# Mcu.net
KiCad netlist of a schematic drawn in Altium Designer
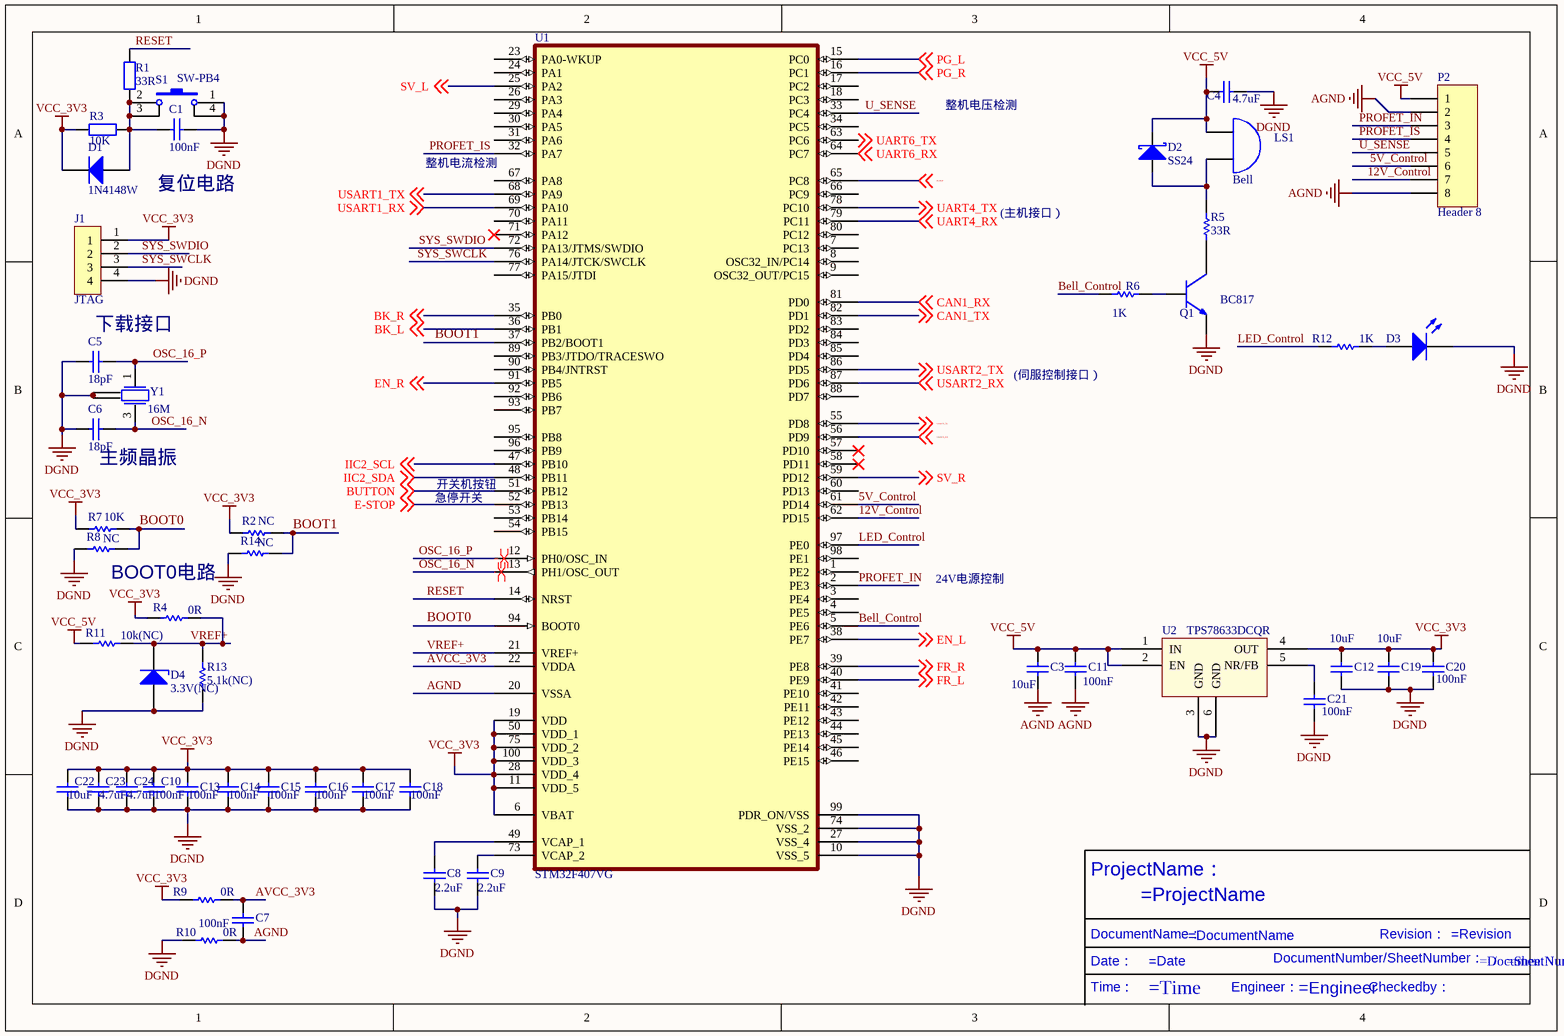
[diagram p0: Mcu.SchDoc]

(export (version "E")
  (design (tool "Eeschema 10.0.6"))
  (components
    (comp (ref "C1")
      (value "100nF")
      (footprint "C-RAD-0805")
      (description "无极性电容")
      (fields (field (name "Comment") "100nF/±10%/50Vdc") (field (name "PUBLISHER") "Altium Limited"))
      (libsource (lib "Compiled_Libraries") (part "Cap"))
    )
    (comp (ref "C3")
      (value "10uF")
      (footprint "C-RAD-0805")
      (description "Capacitor")
      (fields (field (name "Comment") "10uF/±10%/50Vdc") (field (name "PUBLISHER") "Altium Limited"))
      (libsource (lib "STS-TDOA") (part "Cap"))
    )
    (comp (ref "C4")
      (value "4.7uF")
      (footprint "C-RAD-0805")
      (description "Capacitor")
      (fields (field (name "Comment") "4.7uF/±10%/50Vdc") (field (name "PUBLISHER") "Altium Limited"))
      (libsource (lib "boocax_schlib") (part "Cap"))
    )
    (comp (ref "C5")
      (value "18pF")
      (footprint "C-RAD-0805")
      (description "无极性电容")
      (fields (field (name "Comment") "18pF/±10%/25Vdc") (field (name "PUBLISHER") "Altium Limited"))
      (libsource (lib "Compiled_Libraries") (part "Cap"))
    )
    (comp (ref "C6")
      (value "18pF")
      (footprint "C-RAD-0805")
      (description "无极性电容")
      (fields (field (name "Comment") "18pF/±10%/25Vdc") (field (name "PUBLISHER") "Altium Limited"))
      (libsource (lib "Compiled_Libraries") (part "Cap"))
    )
    (comp (ref "C7")
      (value "100nF")
      (footprint "C-RAD-0805")
      (description "Capacitor")
      (fields (field (name "Comment") "100nF/±10%/50Vdc") (field (name "PUBLISHER") "Altium Limited"))
      (libsource (lib "boocax_schlib") (part "Cap"))
    )
    (comp (ref "C8")
      (value "2.2uF")
      (footprint "C-RAD-0805")
      (description "Capacitor")
      (fields (field (name "Comment") "2.2uF/±10%/50Vdc") (field (name "PUBLISHER") "Altium Limited"))
      (libsource (lib "boocax_schlib") (part "Cap"))
    )
    (comp (ref "C9")
      (value "2.2uF")
      (footprint "C-RAD-0805")
      (description "Capacitor")
      (fields (field (name "Comment") "2.2uF/±10%/50Vdc") (field (name "PUBLISHER") "Altium Limited"))
      (libsource (lib "boocax_schlib") (part "Cap"))
    )
    (comp (ref "C10")
      (value "100nF")
      (footprint "C-RAD-0805")
      (description "Capacitor")
      (fields (field (name "Comment") "100nF/±10%/50Vdc") (field (name "PUBLISHER") "Altium Limited"))
      (libsource (lib "boocax_schlib") (part "Cap"))
    )
    (comp (ref "C11")
      (value "100nF")
      (footprint "C-RAD-0805")
      (description "Capacitor")
      (fields (field (name "Comment") "100nF/±10%/50Vdc") (field (name "PUBLISHER") "Altium Limited"))
      (libsource (lib "STS-TDOA") (part "Cap"))
    )
    (comp (ref "C12")
      (value "10uF")
      (footprint "C-RAD-0805")
      (description "Capacitor,33uF / ESR 1.69m /10Vdc,C2012X5R1A336M125AC")
      (fields (field (name "Comment") "10uF/±10%/50Vdc") (field (name "PUBLISHER") "Altium Limited"))
      (libsource (lib "STS-TDOA") (part "Cap"))
    )
    (comp (ref "C13")
      (value "100nF")
      (footprint "C-RAD-0805")
      (description "Capacitor")
      (fields (field (name "Comment") "100nF/±10%/50Vdc") (field (name "PUBLISHER") "Altium Limited"))
      (libsource (lib "boocax_schlib") (part "Cap"))
    )
    (comp (ref "C14")
      (value "100nF")
      (footprint "C-RAD-0805")
      (description "Capacitor")
      (fields (field (name "Comment") "100nF/±10%/50Vdc") (field (name "PUBLISHER") "Altium Limited"))
      (libsource (lib "boocax_schlib") (part "Cap"))
    )
    (comp (ref "C15")
      (value "100nF")
      (footprint "C-RAD-0805")
      (description "Capacitor")
      (fields (field (name "Comment") "100nF/±10%/50Vdc") (field (name "PUBLISHER") "Altium Limited"))
      (libsource (lib "boocax_schlib") (part "Cap"))
    )
    (comp (ref "C16")
      (value "100nF")
      (footprint "C-RAD-0805")
      (description "Capacitor")
      (fields (field (name "Comment") "100nF/±10%/50Vdc") (field (name "PUBLISHER") "Altium Limited"))
      (libsource (lib "boocax_schlib") (part "Cap"))
    )
    (comp (ref "C17")
      (value "100nF")
      (footprint "C-RAD-0805")
      (description "Capacitor")
      (fields (field (name "Comment") "100nF/±10%/50Vdc") (field (name "PUBLISHER") "Altium Limited"))
      (libsource (lib "boocax_schlib") (part "Cap"))
    )
    (comp (ref "C18")
      (value "100nF")
      (footprint "C-RAD-0805")
      (description "Capacitor")
      (fields (field (name "Comment") "100nF/±10%/50Vdc") (field (name "PUBLISHER") "Altium Limited"))
      (libsource (lib "boocax_schlib") (part "Cap"))
    )
    (comp (ref "C19")
      (value "10uF")
      (footprint "C-RAD-0805")
      (description "Capacitor,33uF / ESR 1.69m /10Vdc,C2012X5R1A336M125AC")
      (fields (field (name "Comment") "10uF/±10%/50Vdc") (field (name "PUBLISHER") "Altium Limited"))
      (libsource (lib "STS-TDOA") (part "Cap"))
    )
    (comp (ref "C20")
      (value "100nF")
      (footprint "C-RAD-0805")
      (description "Capacitor")
      (fields (field (name "Comment") "100nF/±10%/50Vdc") (field (name "PUBLISHER") "Altium Limited"))
      (libsource (lib "STS-TDOA") (part "Cap"))
    )
    (comp (ref "C21")
      (value "100nF")
      (footprint "C-RAD-0805")
      (description "Capacitor")
      (fields (field (name "Comment") "100nF/±10%/50Vdc") (field (name "PUBLISHER") "Altium Limited"))
      (libsource (lib "STS-TDOA") (part "Cap"))
    )
    (comp (ref "C22")
      (value "10uF")
      (footprint "C-RAD-0805")
      (description "Capacitor")
      (fields (field (name "Comment") "10uF/±10%/50Vdc") (field (name "PUBLISHER") "Altium Limited"))
      (libsource (lib "boocax_schlib") (part "Cap"))
    )
    (comp (ref "C23")
      (value "4.7uF")
      (footprint "C-RAD-0805")
      (description "Capacitor")
      (fields (field (name "Comment") "4.7uF/±10%/50Vdc") (field (name "PUBLISHER") "Altium Limited"))
      (libsource (lib "boocax_schlib") (part "Cap"))
    )
    (comp (ref "C24")
      (value "4.7uF")
      (footprint "C-RAD-0805")
      (description "Capacitor")
      (fields (field (name "Comment") "4.7uF/±10%/50Vdc") (field (name "PUBLISHER") "Altium Limited"))
      (libsource (lib "boocax_schlib") (part "Cap"))
    )
    (comp (ref "D1")
      (value "1N4148W")
      (footprint "DIODE-1206")
      (description "二极管")
      (fields (field (name "PUBLISHER") "Altium Limited"))
      (libsource (lib "founder") (part "Diode"))
    )
    (comp (ref "D2")
      (value "SS24")
      (footprint "DIODE-SMA")
      (description "肖特基二极管")
      (fields (field (name "Comment") "Diode-Schottky") (field (name "PUBLISHER") "Altium Limited"))
      (libsource (lib "boocax_schlib-20171017-1-dkw") (part "Diode-Schottky"))
    )
    (comp (ref "D3")
      (value "LED0")
      (footprint "LED_0805")
      (description "发光二极管")
      (fields (field (name "PUBLISHER") "Altium Limited"))
      (libsource (lib "founder") (part "LED0"))
    )
    (comp (ref "D4")
      (value "3.3V(NC)")
      (footprint "DIODE-1206")
      (description "稳压二极管")
      (fields (field (name "Comment") "Diode-Z") (field (name "PUBLISHER") "Altium Limited"))
      (libsource (lib "Fszhang") (part "Diode-Z"))
    )
    (comp (ref "J1")
      (value "JTAG")
      (footprint "PORT-SIP4-2.54")
      (libsource (lib "boocax_schlib") (part "Conn_1*4_1"))
    )
    (comp (ref "LS1")
      (value "Bell")
      (footprint "PIN2")
      (description "Electrical Bell")
      (fields (field (name "PUBLISHER") "Altium Limited"))
      (libsource (lib "Miscellaneous Devices") (part "Bell"))
    )
    (comp (ref "P2")
      (value "Header 8")
      (footprint "SM08B-PBV")
      (description "Header, 8-Pin")
      (fields (field (name "PUBLISHER") "Altium Limited"))
      (libsource (lib "fszhang") (part "Header 8"))
    )
    (comp (ref "Q1")
      (value "BC817")
      (footprint "SOT-23_N")
      (description "NPN 45V 功耗 310mW")
      (libsource (lib "Schlib1") (part "mNPN"))
    )
    (comp (ref "R1")
      (value "33R")
      (footprint "0805-1")
      (description "贴片电阻")
      (fields (field (name "Comment") "33R 5% 1/16W 0805") (field (name "PUBLISHER") "Altium Limited"))
      (libsource (lib "Compiled_Libraries") (part "Res1"))
    )
    (comp (ref "R2")
      (value "NC")
      (footprint "0805-1")
      (description "Resistor")
      (fields (field (name "Comment") "10K 5% 1/16W 0805(NC)") (field (name "PUBLISHER") "Altium Limited"))
      (libsource (lib "boocax_schlib") (part "Res1"))
    )
    (comp (ref "R3")
      (value "10K")
      (footprint "0805-1")
      (description "贴片电阻")
      (fields (field (name "Comment") "10K 5% 1/16W 0805") (field (name "PUBLISHER") "Altium Limited"))
      (libsource (lib "") (part "Res1_1"))
    )
    (comp (ref "R4")
      (value "0R")
      (footprint "0805-1")
      (description "Resistor")
      (fields (field (name "Comment") "0R 5% 1/16W 0805(NC)") (field (name "PUBLISHER") "Altium Limited"))
      (libsource (lib "boocax_schlib") (part "Res1"))
    )
    (comp (ref "R5")
      (value "33R")
      (footprint "0805-1")
      (description "Resistor")
      (fields (field (name "Comment") "33R 5% 1/16W 0805") (field (name "PUBLISHER") "Altium Limited"))
      (libsource (lib "boocax_schlib") (part "Res1"))
    )
    (comp (ref "R6")
      (value "1K")
      (footprint "0805-1")
      (description "Resistor")
      (fields (field (name "Comment") "1K 5% 1/16W 0805") (field (name "PUBLISHER") "Altium Limited"))
      (libsource (lib "boocax_schlib") (part "Res1"))
    )
    (comp (ref "R7")
      (value "10K")
      (footprint "0805-1")
      (description "Resistor")
      (fields (field (name "Comment") "10K 5% 1/16W 0805") (field (name "PUBLISHER") "Altium Limited"))
      (libsource (lib "boocax_schlib") (part "Res1"))
    )
    (comp (ref "R8")
      (value "NC")
      (footprint "0805-1")
      (description "Resistor")
      (fields (field (name "Comment") "10K 5% 1/16W 0805(NC)") (field (name "PUBLISHER") "Altium Limited"))
      (libsource (lib "boocax_schlib") (part "Res1"))
    )
    (comp (ref "R9")
      (value "0R")
      (footprint "0805-1")
      (description "Resistor")
      (fields (field (name "Comment") "0R 5% 1/16W 0805") (field (name "PUBLISHER") "Altium Limited"))
      (libsource (lib "boocax_schlib") (part "Res1"))
    )
    (comp (ref "R10")
      (value "0R")
      (footprint "0805-1")
      (description "Resistor")
      (fields (field (name "Comment") "0R 5% 1/16W 0805") (field (name "PUBLISHER") "Altium Limited"))
      (libsource (lib "boocax_schlib") (part "Res1"))
    )
    (comp (ref "R11")
      (value "10k(NC)")
      (footprint "0805-1")
      (description "Resistor")
      (fields (field (name "Comment") "10K 5% 1/16W 0805(NC)") (field (name "PUBLISHER") "Altium Limited"))
      (libsource (lib "boocax_schlib") (part "Res1"))
    )
    (comp (ref "R12")
      (value "1K")
      (footprint "0805-1")
      (description "Resistor")
      (fields (field (name "Comment") "1K 5% 1/16W 0805") (field (name "PUBLISHER") "Altium Limited"))
      (libsource (lib "boocax_schlib") (part "Res1"))
    )
    (comp (ref "R13")
      (value "5.1k(NC)")
      (footprint "0805-1")
      (description "Resistor")
      (fields (field (name "Comment") "5.1K 5% 1/16W 0805(NC)") (field (name "PUBLISHER") "Altium Limited"))
      (libsource (lib "boocax_schlib") (part "Res1"))
    )
    (comp (ref "R14")
      (value "NC")
      (footprint "0805-1")
      (description "Resistor")
      (fields (field (name "Comment") "10K 5% 1/16W 0805(NC)") (field (name "PUBLISHER") "Altium Limited"))
      (libsource (lib "boocax_schlib") (part "Res1"))
    )
    (comp (ref "S1")
      (value "SW-PB4")
      (footprint "RESET-SMD-1O4")
      (description "微动开关")
      (fields (field (name "PUBLISHER") "Altium Limited"))
      (libsource (lib "boocax_schlib") (part "SW-PB4"))
    )
    (comp (ref "U1")
      (value "STM32F407VG")
      (footprint "100T1_N")
      (description "主控MCU")
      (libsource (lib "boocax_schlib") (part "STM32F407VG"))
    )
    (comp (ref "U2")
      (value "TPS78633DCQR")
      (footprint "SOT-223-G6")
      (description "3.3V稳压芯片 1.5A输出")
      (fields (field (name "PUBLISHER") "*"))
      (libsource (lib "Compiled_Libraries") (part "TPS78633DCQR"))
    )
    (comp (ref "Y1")
      (value "16M")
      (footprint "EPSON-16M")
      (description "晶振")
      (fields (field (name "Comment") "XTAL-16M"))
      (libsource (lib "fszhang") (part "XTAL-4PIN"))
    )
  )
  (nets
    (net (code "1") (name "/5V_Control") (class "Default")
      (node (ref "P2") (pin "6") (pinfunction "6_6") (pintype "passive"))
      (node (ref "U1") (pin "61") (pinfunction "PD14_61") (pintype "bidirectional"))
    )
    (net (code "2") (name "/12V_Control") (class "Default")
      (node (ref "P2") (pin "7") (pinfunction "7_7") (pintype "passive"))
      (node (ref "U1") (pin "62") (pinfunction "PD15_62") (pintype "bidirectional"))
    )
    (net (code "11") (name "/AVCC_3V3") (class "Default")
      (node (ref "C7") (pin "2") (pinfunction "2_2") (pintype "passive"))
      (node (ref "R9") (pin "1") (pinfunction "1_1") (pintype "passive"))
      (node (ref "U1") (pin "22") (pinfunction "VDDA_22") (pintype "power_in"))
    )
    (net (code "12") (name "/BOOT0") (class "Default")
      (node (ref "R7") (pin "2") (pinfunction "2_2") (pintype "passive"))
      (node (ref "R8") (pin "1") (pinfunction "1_1") (pintype "passive"))
      (node (ref "U1") (pin "94") (pinfunction "BOOT0_94") (pintype "input"))
    )
    (net (code "13") (name "/BOOT1") (class "Default")
      (node (ref "R14") (pin "1") (pinfunction "1_1") (pintype "passive"))
      (node (ref "R2") (pin "2") (pinfunction "2_2") (pintype "passive"))
      (node (ref "U1") (pin "37") (pinfunction "PB2/BOOT1_37") (pintype "bidirectional"))
    )
    (net (code "14") (name "/Bell_Control") (class "Default")
      (node (ref "R6") (pin "2") (pinfunction "2_2") (pintype "passive"))
      (node (ref "U1") (pin "5") (pinfunction "PE6_5") (pintype "bidirectional"))
    )
    (net (code "20") (name "/LED_Control") (class "Default")
      (node (ref "R12") (pin "2") (pinfunction "2_2") (pintype "passive"))
      (node (ref "U1") (pin "97") (pinfunction "PE0_97") (pintype "bidirectional"))
    )
    (net (code "21") (name "/OSC_16_N") (class "Default")
      (node (ref "C6") (pin "1") (pinfunction "1_1") (pintype "passive"))
      (node (ref "U1") (pin "13") (pinfunction "PH1/OSC_OUT_13") (pintype "output"))
      (node (ref "Y1") (pin "3") (pinfunction "3_3") (pintype "passive"))
    )
    (net (code "22") (name "/OSC_16_P") (class "Default")
      (node (ref "C5") (pin "2") (pinfunction "2_2") (pintype "passive"))
      (node (ref "U1") (pin "12") (pinfunction "PH0/OSC_IN_12") (pintype "input"))
      (node (ref "Y1") (pin "1") (pinfunction "1_1") (pintype "passive"))
    )
    (net (code "23") (name "/PROFET_IN") (class "Default")
      (node (ref "P2") (pin "3") (pinfunction "3_3") (pintype "passive"))
      (node (ref "U1") (pin "2") (pinfunction "PE3_2") (pintype "bidirectional"))
    )
    (net (code "24") (name "/PROFET_IS") (class "Default")
      (node (ref "P2") (pin "4") (pinfunction "4_4") (pintype "passive"))
      (node (ref "U1") (pin "32") (pinfunction "PA7_32") (pintype "bidirectional"))
    )
    (net (code "26") (name "/RESET") (class "Default")
      (node (ref "R1") (pin "1") (pinfunction "1_1") (pintype "passive"))
      (node (ref "U1") (pin "14") (pinfunction "NRST_14") (pintype "bidirectional"))
    )
    (net (code "28") (name "/SYS_SWCLK") (class "Default")
      (node (ref "J1") (pin "3") (pinfunction "3_3") (pintype "passive"))
      (node (ref "U1") (pin "76") (pinfunction "PA14/JTCK/SWCLK_76") (pintype "bidirectional"))
    )
    (net (code "29") (name "/SYS_SWDIO") (class "Default")
      (node (ref "J1") (pin "2") (pinfunction "2_2") (pintype "passive"))
      (node (ref "U1") (pin "72") (pinfunction "PA13/JTMS/SWDIO_72") (pintype "bidirectional"))
    )
    (net (code "31") (name "/U_SENSE") (class "Default")
      (node (ref "P2") (pin "5") (pinfunction "5_5") (pintype "passive"))
      (node (ref "U1") (pin "33") (pinfunction "PC4_33") (pintype "bidirectional"))
    )
    (net (code "32") (name "/VREF+") (class "Default")
      (node (ref "D4") (pin "2") (pinfunction "K_2") (pintype "passive"))
      (node (ref "R11") (pin "1") (pinfunction "1_1") (pintype "passive"))
      (node (ref "R13") (pin "2") (pinfunction "2_2") (pintype "passive"))
      (node (ref "R4") (pin "1") (pinfunction "1_1") (pintype "passive"))
      (node (ref "U1") (pin "21") (pinfunction "VREF+_21") (pintype "power_in"))
    )
    (net (code "34") (name "AGND") (class "Default")
      (node (ref "C11") (pin "1") (pinfunction "1_1") (pintype "passive"))
      (node (ref "C3") (pin "1") (pinfunction "1_1") (pintype "passive"))
      (node (ref "C7") (pin "1") (pinfunction "1_1") (pintype "passive"))
      (node (ref "P2") (pin "2") (pinfunction "2_2") (pintype "passive"))
      (node (ref "P2") (pin "8") (pinfunction "8_8") (pintype "passive"))
      (node (ref "R10") (pin "1") (pinfunction "1_1") (pintype "passive"))
      (node (ref "U1") (pin "20") (pinfunction "VSSA_20") (pintype "power_in"))
    )
    (net (code "35") (name "B-STOP") (class "Default")
      (node (ref "U1") (pin "65") (pinfunction "PC8_65") (pintype "bidirectional"))
    )
    (net (code "36") (name "BK_L") (class "Default")
      (node (ref "U1") (pin "36") (pinfunction "PB1_36") (pintype "bidirectional"))
    )
    (net (code "37") (name "BK_R") (class "Default")
      (node (ref "U1") (pin "35") (pinfunction "PB0_35") (pintype "bidirectional"))
    )
    (net (code "38") (name "BUTTON") (class "Default")
      (node (ref "U1") (pin "51") (pinfunction "PB12_51") (pintype "bidirectional"))
    )
    (net (code "39") (name "CAN1_RX") (class "Default")
      (node (ref "U1") (pin "81") (pinfunction "PD0_81") (pintype "bidirectional"))
    )
    (net (code "40") (name "CAN1_TX") (class "Default")
      (node (ref "U1") (pin "82") (pinfunction "PD1_82") (pintype "bidirectional"))
    )
    (net (code "41") (name "DGND") (class "Default")
      (node (ref "C1") (pin "1") (pinfunction "1_1") (pintype "passive"))
      (node (ref "C10") (pin "2") (pinfunction "2_2") (pintype "passive"))
      (node (ref "C12") (pin "1") (pinfunction "1_1") (pintype "passive"))
      (node (ref "C13") (pin "2") (pinfunction "2_2") (pintype "passive"))
      (node (ref "C14") (pin "2") (pinfunction "2_2") (pintype "passive"))
      (node (ref "C15") (pin "2") (pinfunction "2_2") (pintype "passive"))
      (node (ref "C16") (pin "2") (pinfunction "2_2") (pintype "passive"))
      (node (ref "C17") (pin "2") (pinfunction "2_2") (pintype "passive"))
      (node (ref "C18") (pin "2") (pinfunction "2_2") (pintype "passive"))
      (node (ref "C19") (pin "1") (pinfunction "1_1") (pintype "passive"))
      (node (ref "C20") (pin "1") (pinfunction "1_1") (pintype "passive"))
      (node (ref "C21") (pin "1") (pinfunction "1_1") (pintype "passive"))
      (node (ref "C22") (pin "2") (pinfunction "2_2") (pintype "passive"))
      (node (ref "C23") (pin "2") (pinfunction "2_2") (pintype "passive"))
      (node (ref "C24") (pin "2") (pinfunction "2_2") (pintype "passive"))
      (node (ref "C4") (pin "1") (pinfunction "1_1") (pintype "passive"))
      (node (ref "C5") (pin "1") (pinfunction "1_1") (pintype "passive"))
      (node (ref "C6") (pin "2") (pinfunction "2_2") (pintype "passive"))
      (node (ref "C8") (pin "2") (pinfunction "2_2") (pintype "passive"))
      (node (ref "C9") (pin "2") (pinfunction "2_2") (pintype "passive"))
      (node (ref "D3") (pin "2") (pinfunction "K_2") (pintype "passive"))
      (node (ref "D4") (pin "1") (pinfunction "A_1") (pintype "passive"))
      (node (ref "J1") (pin "4") (pinfunction "4_4") (pintype "passive"))
      (node (ref "Q1") (pin "2") (pinfunction "E_2") (pintype "passive"))
      (node (ref "R10") (pin "2") (pinfunction "2_2") (pintype "passive"))
      (node (ref "R13") (pin "1") (pinfunction "1_1") (pintype "passive"))
      (node (ref "R14") (pin "2") (pinfunction "2_2") (pintype "passive"))
      (node (ref "R8") (pin "2") (pinfunction "2_2") (pintype "passive"))
      (node (ref "S1") (pin "1") (pinfunction "1_1") (pintype "passive"))
      (node (ref "S1") (pin "4") (pinfunction "4_4") (pintype "passive"))
      (node (ref "U1") (pin "10") (pinfunction "VSS_5_10") (pintype "passive"))
      (node (ref "U1") (pin "27") (pinfunction "VSS_4_27") (pintype "passive"))
      (node (ref "U1") (pin "74") (pinfunction "VSS_2_74") (pintype "passive"))
      (node (ref "U1") (pin "99") (pinfunction "PDR_ON/VSS_99") (pintype "power_in"))
      (node (ref "U2") (pin "3") (pinfunction "GND_3") (pintype "power_in"))
      (node (ref "U2") (pin "6") (pinfunction "GND_6") (pintype "power_in"))
      (node (ref "Y1") (pin "2") (pinfunction "2_2") (pintype "passive"))
      (node (ref "Y1") (pin "4") (pinfunction "4_4") (pintype "passive"))
    )
    (net (code "42") (name "E-STOP") (class "Default")
      (node (ref "U1") (pin "52") (pinfunction "PB13_52") (pintype "bidirectional"))
    )
    (net (code "43") (name "EN_L") (class "Default")
      (node (ref "U1") (pin "38") (pinfunction "PE7_38") (pintype "bidirectional"))
    )
    (net (code "44") (name "EN_R") (class "Default")
      (node (ref "U1") (pin "91") (pinfunction "PB5_91") (pintype "bidirectional"))
    )
    (net (code "45") (name "FR_L") (class "Default")
      (node (ref "U1") (pin "40") (pinfunction "PE9_40") (pintype "bidirectional"))
    )
    (net (code "46") (name "FR_R") (class "Default")
      (node (ref "U1") (pin "39") (pinfunction "PE8_39") (pintype "bidirectional"))
    )
    (net (code "47") (name "IIC2_SCL") (class "Default")
      (node (ref "U1") (pin "47") (pinfunction "PB10_47") (pintype "bidirectional"))
    )
    (net (code "48") (name "IIC2_SDA") (class "Default")
      (node (ref "U1") (pin "48") (pinfunction "PB11_48") (pintype "bidirectional"))
    )
    (net (code "49") (name "Net-(D1-A)") (class "Default")
      (node (ref "C1") (pin "2") (pinfunction "2_2") (pintype "passive"))
      (node (ref "D1") (pin "1") (pinfunction "A_1") (pintype "passive"))
      (node (ref "R1") (pin "2") (pinfunction "2_2") (pintype "passive"))
      (node (ref "R3") (pin "1") (pinfunction "1_1") (pintype "passive"))
      (node (ref "S1") (pin "2") (pinfunction "2_2") (pintype "passive"))
      (node (ref "S1") (pin "3") (pinfunction "3_3") (pintype "passive"))
    )
    (net (code "50") (name "Net-(D2-A)") (class "Default")
      (node (ref "D2") (pin "1") (pinfunction "A_1") (pintype "passive"))
      (node (ref "LS1") (pin "2") (pinfunction "B_2") (pintype "passive"))
      (node (ref "R5") (pin "1") (pinfunction "1_1") (pintype "passive"))
    )
    (net (code "51") (name "Net-(D3-A)") (class "Default")
      (node (ref "D3") (pin "1") (pinfunction "A_1") (pintype "passive"))
      (node (ref "R12") (pin "1") (pinfunction "1_1") (pintype "passive"))
    )
    (net (code "52") (name "Net-(Q1-B)") (class "Default")
      (node (ref "Q1") (pin "1") (pinfunction "B_1") (pintype "passive"))
      (node (ref "R6") (pin "1") (pinfunction "1_1") (pintype "passive"))
    )
    (net (code "53") (name "Net-(Q1-C)") (class "Default")
      (node (ref "Q1") (pin "3") (pinfunction "C_3") (pintype "passive"))
      (node (ref "R5") (pin "2") (pinfunction "2_2") (pintype "passive"))
    )
    (net (code "54") (name "Net-(U1-VCAP_1)") (class "Default")
      (node (ref "C8") (pin "1") (pinfunction "1_1") (pintype "passive"))
      (node (ref "U1") (pin "49") (pinfunction "VCAP_1_49") (pintype "power_in"))
    )
    (net (code "55") (name "Net-(U1-VCAP_2)") (class "Default")
      (node (ref "C9") (pin "1") (pinfunction "1_1") (pintype "passive"))
      (node (ref "U1") (pin "73") (pinfunction "VCAP_2_73") (pintype "power_in"))
    )
    (net (code "56") (name "Net-(U2-NR{slash}FB)") (class "Default")
      (node (ref "C21") (pin "2") (pinfunction "2_2") (pintype "passive"))
      (node (ref "U2") (pin "5") (pinfunction "NR/FB_5") (pintype "power_in"))
    )
    (net (code "57") (name "PG_L") (class "Default")
      (node (ref "U1") (pin "15") (pinfunction "PC0_15") (pintype "bidirectional"))
    )
    (net (code "58") (name "PG_R") (class "Default")
      (node (ref "U1") (pin "16") (pinfunction "PC1_16") (pintype "bidirectional"))
    )
    (net (code "59") (name "SV_L") (class "Default")
      (node (ref "U1") (pin "25") (pinfunction "PA2_25") (pintype "bidirectional"))
    )
    (net (code "60") (name "SV_R") (class "Default")
      (node (ref "U1") (pin "59") (pinfunction "PD12_59") (pintype "bidirectional"))
    )
    (net (code "61") (name "UART4_RX") (class "Default")
      (node (ref "U1") (pin "79") (pinfunction "PC11_79") (pintype "bidirectional"))
    )
    (net (code "62") (name "UART4_TX") (class "Default")
      (node (ref "U1") (pin "78") (pinfunction "PC10_78") (pintype "bidirectional"))
    )
    (net (code "63") (name "UART6_RX") (class "Default")
      (node (ref "U1") (pin "64") (pinfunction "PC7_64") (pintype "bidirectional"))
    )
    (net (code "64") (name "UART6_TX") (class "Default")
      (node (ref "U1") (pin "63") (pinfunction "PC6_63") (pintype "bidirectional"))
    )
    (net (code "65") (name "USART1_RX") (class "Default")
      (node (ref "U1") (pin "69") (pinfunction "PA10_69") (pintype "bidirectional"))
    )
    (net (code "66") (name "USART1_TX") (class "Default")
      (node (ref "U1") (pin "68") (pinfunction "PA9_68") (pintype "bidirectional"))
    )
    (net (code "67") (name "USART2_RX") (class "Default")
      (node (ref "U1") (pin "87") (pinfunction "PD6_87") (pintype "bidirectional"))
    )
    (net (code "68") (name "USART2_TX") (class "Default")
      (node (ref "U1") (pin "86") (pinfunction "PD5_86") (pintype "bidirectional"))
    )
    (net (code "69") (name "USART3_RX") (class "Default")
      (node (ref "U1") (pin "56") (pinfunction "PD9_56") (pintype "bidirectional"))
    )
    (net (code "70") (name "USART3_TX") (class "Default")
      (node (ref "U1") (pin "55") (pinfunction "PD8_55") (pintype "bidirectional"))
    )
    (net (code "71") (name "VCC_3V3") (class "Default")
      (node (ref "C10") (pin "1") (pinfunction "1_1") (pintype "passive"))
      (node (ref "C12") (pin "2") (pinfunction "2_2") (pintype "passive"))
      (node (ref "C13") (pin "1") (pinfunction "1_1") (pintype "passive"))
      (node (ref "C14") (pin "1") (pinfunction "1_1") (pintype "passive"))
      (node (ref "C15") (pin "1") (pinfunction "1_1") (pintype "passive"))
      (node (ref "C16") (pin "1") (pinfunction "1_1") (pintype "passive"))
      (node (ref "C17") (pin "1") (pinfunction "1_1") (pintype "passive"))
      (node (ref "C18") (pin "1") (pinfunction "1_1") (pintype "passive"))
      (node (ref "C19") (pin "2") (pinfunction "2_2") (pintype "passive"))
      (node (ref "C20") (pin "2") (pinfunction "2_2") (pintype "passive"))
      (node (ref "C22") (pin "1") (pinfunction "1_1") (pintype "passive"))
      (node (ref "C23") (pin "1") (pinfunction "1_1") (pintype "passive"))
      (node (ref "C24") (pin "1") (pinfunction "1_1") (pintype "passive"))
      (node (ref "D1") (pin "2") (pinfunction "K_2") (pintype "passive"))
      (node (ref "J1") (pin "1") (pinfunction "1_1") (pintype "passive"))
      (node (ref "R2") (pin "1") (pinfunction "1_1") (pintype "passive"))
      (node (ref "R3") (pin "2") (pinfunction "2_2") (pintype "passive"))
      (node (ref "R4") (pin "2") (pinfunction "2_2") (pintype "passive"))
      (node (ref "R7") (pin "1") (pinfunction "1_1") (pintype "passive"))
      (node (ref "R9") (pin "2") (pinfunction "2_2") (pintype "passive"))
      (node (ref "U1") (pin "100") (pinfunction "VDD_3_100") (pintype "power_in"))
      (node (ref "U1") (pin "11") (pinfunction "VDD_5_11") (pintype "power_in"))
      (node (ref "U1") (pin "19") (pinfunction "VDD_19") (pintype "power_in"))
      (node (ref "U1") (pin "28") (pinfunction "VDD_4_28") (pintype "power_in"))
      (node (ref "U1") (pin "50") (pinfunction "VDD_1_50") (pintype "power_in"))
      (node (ref "U1") (pin "6") (pinfunction "VBAT_6") (pintype "power_in"))
      (node (ref "U1") (pin "75") (pinfunction "VDD_2_75") (pintype "power_in"))
      (node (ref "U2") (pin "4") (pinfunction "OUT_4") (pintype "power_in"))
    )
    (net (code "72") (name "VCC_5V") (class "Default")
      (node (ref "C11") (pin "2") (pinfunction "2_2") (pintype "passive"))
      (node (ref "C3") (pin "2") (pinfunction "2_2") (pintype "passive"))
      (node (ref "C4") (pin "2") (pinfunction "2_2") (pintype "passive"))
      (node (ref "D2") (pin "2") (pinfunction "K_2") (pintype "passive"))
      (node (ref "LS1") (pin "1") (pinfunction "A_1") (pintype "passive"))
      (node (ref "P2") (pin "1") (pinfunction "1_1") (pintype "passive"))
      (node (ref "R11") (pin "2") (pinfunction "2_2") (pintype "passive"))
      (node (ref "U2") (pin "1") (pinfunction "IN_1") (pintype "power_in"))
      (node (ref "U2") (pin "2") (pinfunction "EN_2") (pintype "power_in"))
    )
    (net (code "73") (name "unconnected-(U1-OSC32_IN{slash}PC14-Pad8)") (class "Default")
      (node (ref "U1") (pin "8") (pinfunction "OSC32_IN/PC14_8") (pintype "bidirectional"))
    )
    (net (code "74") (name "unconnected-(U1-OSC32_OUT{slash}PC15-Pad9)") (class "Default")
      (node (ref "U1") (pin "9") (pinfunction "OSC32_OUT/PC15_9") (pintype "bidirectional"))
    )
    (net (code "75") (name "unconnected-(U1-PA0-WKUP-Pad23)") (class "Default")
      (node (ref "U1") (pin "23") (pinfunction "PA0-WKUP_23") (pintype "bidirectional"))
    )
    (net (code "76") (name "unconnected-(U1-PA1-Pad24)") (class "Default")
      (node (ref "U1") (pin "24") (pinfunction "PA1_24") (pintype "bidirectional"))
    )
    (net (code "77") (name "unconnected-(U1-PA3-Pad26)") (class "Default")
      (node (ref "U1") (pin "26") (pinfunction "PA3_26") (pintype "bidirectional"))
    )
    (net (code "78") (name "unconnected-(U1-PA4-Pad29)") (class "Default")
      (node (ref "U1") (pin "29") (pinfunction "PA4_29") (pintype "bidirectional"))
    )
    (net (code "79") (name "unconnected-(U1-PA5-Pad30)") (class "Default")
      (node (ref "U1") (pin "30") (pinfunction "PA5_30") (pintype "bidirectional"))
    )
    (net (code "80") (name "unconnected-(U1-PA6-Pad31)") (class "Default")
      (node (ref "U1") (pin "31") (pinfunction "PA6_31") (pintype "bidirectional"))
    )
    (net (code "81") (name "unconnected-(U1-PA8-Pad67)") (class "Default")
      (node (ref "U1") (pin "67") (pinfunction "PA8_67") (pintype "bidirectional"))
    )
    (net (code "82") (name "unconnected-(U1-PA11-Pad70)") (class "Default")
      (node (ref "U1") (pin "70") (pinfunction "PA11_70") (pintype "bidirectional"))
    )
    (net (code "83") (name "unconnected-(U1-PA12-Pad71)") (class "Default")
      (node (ref "U1") (pin "71") (pinfunction "PA12_71") (pintype "bidirectional+no_connect"))
    )
    (net (code "84") (name "unconnected-(U1-PA15{slash}JTDI-Pad77)") (class "Default")
      (node (ref "U1") (pin "77") (pinfunction "PA15/JTDI_77") (pintype "bidirectional"))
    )
    (net (code "85") (name "unconnected-(U1-PB3{slash}JTDO{slash}TRACESWO-Pad89)") (class "Default")
      (node (ref "U1") (pin "89") (pinfunction "PB3/JTDO/TRACESWO_89") (pintype "bidirectional"))
    )
    (net (code "86") (name "unconnected-(U1-PB4{slash}JNTRST-Pad90)") (class "Default")
      (node (ref "U1") (pin "90") (pinfunction "PB4/JNTRST_90") (pintype "bidirectional"))
    )
    (net (code "87") (name "unconnected-(U1-PB6-Pad92)") (class "Default")
      (node (ref "U1") (pin "92") (pinfunction "PB6_92") (pintype "bidirectional"))
    )
    (net (code "88") (name "unconnected-(U1-PB7-Pad93)") (class "Default")
      (node (ref "U1") (pin "93") (pinfunction "PB7_93") (pintype "bidirectional"))
    )
    (net (code "89") (name "unconnected-(U1-PB8-Pad95)") (class "Default")
      (node (ref "U1") (pin "95") (pinfunction "PB8_95") (pintype "bidirectional"))
    )
    (net (code "90") (name "unconnected-(U1-PB9-Pad96)") (class "Default")
      (node (ref "U1") (pin "96") (pinfunction "PB9_96") (pintype "bidirectional"))
    )
    (net (code "91") (name "unconnected-(U1-PB14-Pad53)") (class "Default")
      (node (ref "U1") (pin "53") (pinfunction "PB14_53") (pintype "bidirectional"))
    )
    (net (code "92") (name "unconnected-(U1-PB15-Pad54)") (class "Default")
      (node (ref "U1") (pin "54") (pinfunction "PB15_54") (pintype "bidirectional"))
    )
    (net (code "93") (name "unconnected-(U1-PC2-Pad17)") (class "Default")
      (node (ref "U1") (pin "17") (pinfunction "PC2_17") (pintype "bidirectional"))
    )
    (net (code "94") (name "unconnected-(U1-PC3-Pad18)") (class "Default")
      (node (ref "U1") (pin "18") (pinfunction "PC3_18") (pintype "bidirectional"))
    )
    (net (code "95") (name "unconnected-(U1-PC5-Pad34)") (class "Default")
      (node (ref "U1") (pin "34") (pinfunction "PC5_34") (pintype "bidirectional"))
    )
    (net (code "96") (name "unconnected-(U1-PC9-Pad66)") (class "Default")
      (node (ref "U1") (pin "66") (pinfunction "PC9_66") (pintype "bidirectional"))
    )
    (net (code "97") (name "unconnected-(U1-PC12-Pad80)") (class "Default")
      (node (ref "U1") (pin "80") (pinfunction "PC12_80") (pintype "bidirectional"))
    )
    (net (code "98") (name "unconnected-(U1-PC13-Pad7)") (class "Default")
      (node (ref "U1") (pin "7") (pinfunction "PC13_7") (pintype "bidirectional"))
    )
    (net (code "99") (name "unconnected-(U1-PD2-Pad83)") (class "Default")
      (node (ref "U1") (pin "83") (pinfunction "PD2_83") (pintype "bidirectional"))
    )
    (net (code "100") (name "unconnected-(U1-PD3-Pad84)") (class "Default")
      (node (ref "U1") (pin "84") (pinfunction "PD3_84") (pintype "bidirectional"))
    )
    (net (code "101") (name "unconnected-(U1-PD4-Pad85)") (class "Default")
      (node (ref "U1") (pin "85") (pinfunction "PD4_85") (pintype "bidirectional"))
    )
    (net (code "102") (name "unconnected-(U1-PD7-Pad88)") (class "Default")
      (node (ref "U1") (pin "88") (pinfunction "PD7_88") (pintype "bidirectional"))
    )
    (net (code "103") (name "unconnected-(U1-PD10-Pad57)") (class "Default")
      (node (ref "U1") (pin "57") (pinfunction "PD10_57") (pintype "bidirectional+no_connect"))
    )
    (net (code "104") (name "unconnected-(U1-PD11-Pad58)") (class "Default")
      (node (ref "U1") (pin "58") (pinfunction "PD11_58") (pintype "bidirectional+no_connect"))
    )
    (net (code "105") (name "unconnected-(U1-PD13-Pad60)") (class "Default")
      (node (ref "U1") (pin "60") (pinfunction "PD13_60") (pintype "bidirectional"))
    )
    (net (code "106") (name "unconnected-(U1-PE1-Pad98)") (class "Default")
      (node (ref "U1") (pin "98") (pinfunction "PE1_98") (pintype "bidirectional"))
    )
    (net (code "107") (name "unconnected-(U1-PE2-Pad1)") (class "Default")
      (node (ref "U1") (pin "1") (pinfunction "PE2_1") (pintype "bidirectional"))
    )
    (net (code "108") (name "unconnected-(U1-PE4-Pad3)") (class "Default")
      (node (ref "U1") (pin "3") (pinfunction "PE4_3") (pintype "bidirectional"))
    )
    (net (code "109") (name "unconnected-(U1-PE5-Pad4)") (class "Default")
      (node (ref "U1") (pin "4") (pinfunction "PE5_4") (pintype "bidirectional"))
    )
    (net (code "110") (name "unconnected-(U1-PE10-Pad41)") (class "Default")
      (node (ref "U1") (pin "41") (pinfunction "PE10_41") (pintype "bidirectional"))
    )
    (net (code "111") (name "unconnected-(U1-PE11-Pad42)") (class "Default")
      (node (ref "U1") (pin "42") (pinfunction "PE11_42") (pintype "bidirectional"))
    )
    (net (code "112") (name "unconnected-(U1-PE12-Pad43)") (class "Default")
      (node (ref "U1") (pin "43") (pinfunction "PE12_43") (pintype "bidirectional"))
    )
    (net (code "113") (name "unconnected-(U1-PE13-Pad44)") (class "Default")
      (node (ref "U1") (pin "44") (pinfunction "PE13_44") (pintype "bidirectional"))
    )
    (net (code "114") (name "unconnected-(U1-PE14-Pad45)") (class "Default")
      (node (ref "U1") (pin "45") (pinfunction "PE14_45") (pintype "bidirectional"))
    )
    (net (code "115") (name "unconnected-(U1-PE15-Pad46)") (class "Default")
      (node (ref "U1") (pin "46") (pinfunction "PE15_46") (pintype "bidirectional"))
    )
  )
)
